# multiplexer.net
KiCad netlist of a schematic drawn in EAGLE
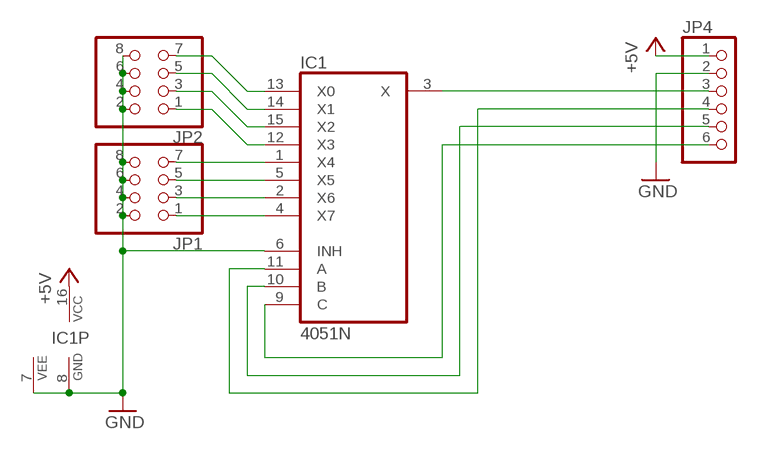
[diagram p0: schematic, sheet 1]

(export (version "E")
  (design (tool "Eeschema 10.0.6"))
  (components
    (comp (ref "IC1")
      (value "4051N")
      (footprint "eagle-import:DIL16")
      (libsource (lib "eagle-import") (part "4051N"))
    )
    (comp (ref "JP1")
      (value "PINHD-2X4/90")
      (footprint "eagle-import:2X04_90")
      (libsource (lib "eagle-import") (part "PINHD-2X4/90"))
    )
    (comp (ref "JP2")
      (value "PINHD-2X4/90")
      (footprint "eagle-import:2X04_90")
      (libsource (lib "eagle-import") (part "PINHD-2X4/90"))
    )
    (comp (ref "JP4")
      (value "PINHD-1X6/90")
      (footprint "eagle-import:1X06_90")
      (libsource (lib "eagle-import") (part "PINHD-1X6/90"))
    )
  )
  (nets
    (net (code "1") (name "+5V") (class "Default")
      (node (ref "IC1") (pin "16") (pinfunction "VCC_16") (pintype "power_in"))
      (node (ref "JP4") (pin "1") (pinfunction "1_1") (pintype "passive"))
    )
    (net (code "2") (name "GND") (class "Default")
      (node (ref "IC1") (pin "6") (pinfunction "INH_6") (pintype "input"))
      (node (ref "IC1") (pin "7") (pinfunction "VEE_7") (pintype "power_in"))
      (node (ref "IC1") (pin "8") (pinfunction "GND_8") (pintype "power_in"))
      (node (ref "JP1") (pin "2") (pinfunction "2_2") (pintype "passive"))
      (node (ref "JP1") (pin "4") (pinfunction "4_4") (pintype "passive"))
      (node (ref "JP1") (pin "6") (pinfunction "6_6") (pintype "passive"))
      (node (ref "JP1") (pin "8") (pinfunction "8_8") (pintype "passive"))
      (node (ref "JP2") (pin "2") (pinfunction "2_2") (pintype "passive"))
      (node (ref "JP2") (pin "4") (pinfunction "4_4") (pintype "passive"))
      (node (ref "JP2") (pin "6") (pinfunction "6_6") (pintype "passive"))
      (node (ref "JP2") (pin "8") (pinfunction "8_8") (pintype "passive"))
      (node (ref "JP4") (pin "2") (pinfunction "2_2") (pintype "passive"))
    )
    (net (code "3") (name "Net-(IC1A-A)") (class "Default")
      (node (ref "IC1") (pin "11") (pinfunction "A_11") (pintype "input"))
      (node (ref "JP4") (pin "4") (pinfunction "4_4") (pintype "passive"))
    )
    (net (code "4") (name "Net-(IC1A-B)") (class "Default")
      (node (ref "IC1") (pin "10") (pinfunction "B_10") (pintype "input"))
      (node (ref "JP4") (pin "5") (pinfunction "5_5") (pintype "passive"))
    )
    (net (code "5") (name "Net-(IC1A-C)") (class "Default")
      (node (ref "IC1") (pin "9") (pinfunction "C_9") (pintype "input"))
      (node (ref "JP4") (pin "6") (pinfunction "6_6") (pintype "passive"))
    )
    (net (code "6") (name "Net-(IC1A-X)") (class "Default")
      (node (ref "IC1") (pin "3") (pinfunction "X_3") (pintype "bidirectional"))
      (node (ref "JP4") (pin "3") (pinfunction "3_3") (pintype "passive"))
    )
    (net (code "7") (name "Net-(IC1A-X0)") (class "Default")
      (node (ref "IC1") (pin "13") (pinfunction "X0_13") (pintype "bidirectional"))
      (node (ref "JP2") (pin "7") (pinfunction "7_7") (pintype "passive"))
    )
    (net (code "8") (name "Net-(IC1A-X1)") (class "Default")
      (node (ref "IC1") (pin "14") (pinfunction "X1_14") (pintype "bidirectional"))
      (node (ref "JP2") (pin "5") (pinfunction "5_5") (pintype "passive"))
    )
    (net (code "9") (name "Net-(IC1A-X2)") (class "Default")
      (node (ref "IC1") (pin "15") (pinfunction "X2_15") (pintype "bidirectional"))
      (node (ref "JP2") (pin "3") (pinfunction "3_3") (pintype "passive"))
    )
    (net (code "10") (name "Net-(IC1A-X3)") (class "Default")
      (node (ref "IC1") (pin "12") (pinfunction "X3_12") (pintype "bidirectional"))
      (node (ref "JP2") (pin "1") (pinfunction "1_1") (pintype "passive"))
    )
    (net (code "11") (name "Net-(IC1A-X4)") (class "Default")
      (node (ref "IC1") (pin "1") (pinfunction "X4_1") (pintype "bidirectional"))
      (node (ref "JP1") (pin "7") (pinfunction "7_7") (pintype "passive"))
    )
    (net (code "12") (name "Net-(IC1A-X5)") (class "Default")
      (node (ref "IC1") (pin "5") (pinfunction "X5_5") (pintype "bidirectional"))
      (node (ref "JP1") (pin "5") (pinfunction "5_5") (pintype "passive"))
    )
    (net (code "13") (name "Net-(IC1A-X6)") (class "Default")
      (node (ref "IC1") (pin "2") (pinfunction "X6_2") (pintype "bidirectional"))
      (node (ref "JP1") (pin "3") (pinfunction "3_3") (pintype "passive"))
    )
    (net (code "14") (name "Net-(IC1A-X7)") (class "Default")
      (node (ref "IC1") (pin "4") (pinfunction "X7_4") (pintype "bidirectional"))
      (node (ref "JP1") (pin "1") (pinfunction "1_1") (pintype "passive"))
    )
  )
)
